# Encoder.net
KiCad netlist of a schematic drawn in Altium Designer
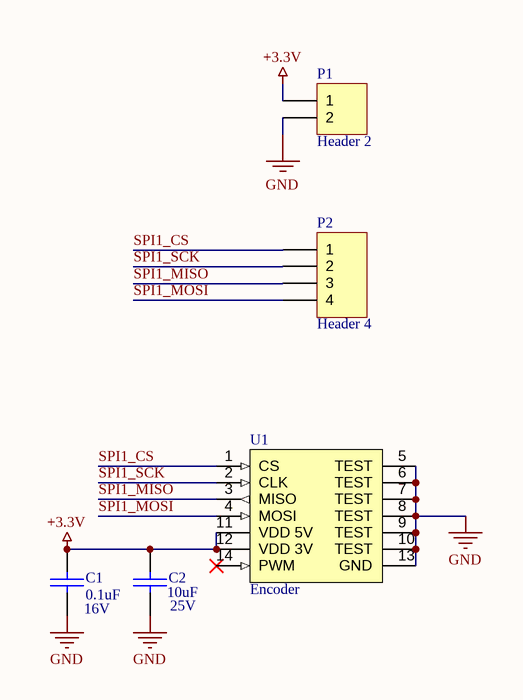
[diagram p0: Encoder.SchDoc]

(export (version "E")
  (design (tool "Eeschema 10.0.6"))
  (components
    (comp (ref "C1")
      (value "0.1uF")
      (footprint "0603 Capicator")
      (description "0.1uF X7R 16V 10% 0603")
      (fields
        (field (name "MANUFACTURER") "Murata Manufacturing")
        (field (name "PART NUMBER") "GRM188R71C104KA01D")
        (field (name "VOLTAGE") "16V")
      )
      (libsource (lib "Karen_Components") (part "Cap 0.1uF (0603)"))
    )
    (comp (ref "C2")
      (value "10uF")
      (footprint "0603 Capicator")
      (description "10uF X5R 25V 20% 0603")
      (fields
        (field (name "MANUFACTURER") "Murata Manufacturing")
        (field (name "PART NUMBER") "GRM188R61E106M")
        (field (name "VOLTAGE") "25V")
      )
      (libsource (lib "Karen_Components") (part "Cap 10uF (0603)"))
    )
    (comp (ref "P1")
      (value "Header 2")
      (footprint "HDR1X2")
      (description "Header, 2-Pin")
      (fields (field (name "PUBLISHER") "Altium Limited"))
      (libsource (lib "Miscellaneous Connectors") (part "Header 2"))
    )
    (comp (ref "P2")
      (value "Header 4")
      (footprint "HDR1X4")
      (description "Header, 4-Pin")
      (fields (field (name "PUBLISHER") "Altium Limited"))
      (libsource (lib "Miscellaneous Connectors") (part "Header 4"))
    )
    (comp (ref "U1")
      (value "Encoder")
      (footprint "TSSOP-14")
      (description "Magnetic Rotary Encoder")
      (fields (field (name "PART NUMBER") "AS5048A") (field (name "MANUFACTURER") "ams"))
      (libsource (lib "Karen_Components") (part "Encoder"))
    )
  )
  (nets
    (net (code "1") (name "+3.3V") (class "Default")
      (node (ref "C1") (pin "1") (pinfunction "1_1") (pintype "passive"))
      (node (ref "C2") (pin "1") (pinfunction "1_1") (pintype "passive"))
      (node (ref "P1") (pin "1") (pinfunction "1_1") (pintype "passive"))
      (node (ref "U1") (pin "11") (pinfunction "VDD_5V_11") (pintype "power_in"))
      (node (ref "U1") (pin "12") (pinfunction "VDD_3V_12") (pintype "power_in"))
    )
    (net (code "2") (name "/SPI1_CS") (class "Default")
      (node (ref "P2") (pin "1") (pinfunction "1_1") (pintype "passive"))
      (node (ref "U1") (pin "1") (pinfunction "CS_1") (pintype "input"))
    )
    (net (code "3") (name "/SPI1_MISO") (class "Default")
      (node (ref "P2") (pin "3") (pinfunction "3_3") (pintype "passive"))
      (node (ref "U1") (pin "3") (pinfunction "MISO_3") (pintype "output"))
    )
    (net (code "4") (name "/SPI1_MOSI") (class "Default")
      (node (ref "P2") (pin "4") (pinfunction "4_4") (pintype "passive"))
      (node (ref "U1") (pin "4") (pinfunction "MOSI_4") (pintype "input"))
    )
    (net (code "5") (name "/SPI1_SCK") (class "Default")
      (node (ref "P2") (pin "2") (pinfunction "2_2") (pintype "passive"))
      (node (ref "U1") (pin "2") (pinfunction "CLK_2") (pintype "input"))
    )
    (net (code "6") (name "GND") (class "Default")
      (node (ref "C1") (pin "2") (pinfunction "2_2") (pintype "passive"))
      (node (ref "C2") (pin "2") (pinfunction "2_2") (pintype "passive"))
      (node (ref "P1") (pin "2") (pinfunction "2_2") (pintype "passive"))
      (node (ref "U1") (pin "10") (pinfunction "TEST_10") (pintype "power_in"))
      (node (ref "U1") (pin "13") (pinfunction "GND_13") (pintype "power_in"))
      (node (ref "U1") (pin "5") (pinfunction "TEST_5") (pintype "power_in"))
      (node (ref "U1") (pin "6") (pinfunction "TEST_6") (pintype "power_in"))
      (node (ref "U1") (pin "7") (pinfunction "TEST_7") (pintype "power_in"))
      (node (ref "U1") (pin "8") (pinfunction "TEST_8") (pintype "power_in"))
      (node (ref "U1") (pin "9") (pinfunction "TEST_9") (pintype "power_in"))
    )
    (net (code "7") (name "unconnected-(U1-PWM-Pad14)") (class "Default")
      (node (ref "U1") (pin "14") (pinfunction "PWM_14") (pintype "input+no_connect"))
    )
  )
)
